# MainPSU.net
KiCad netlist of a schematic drawn in EAGLE
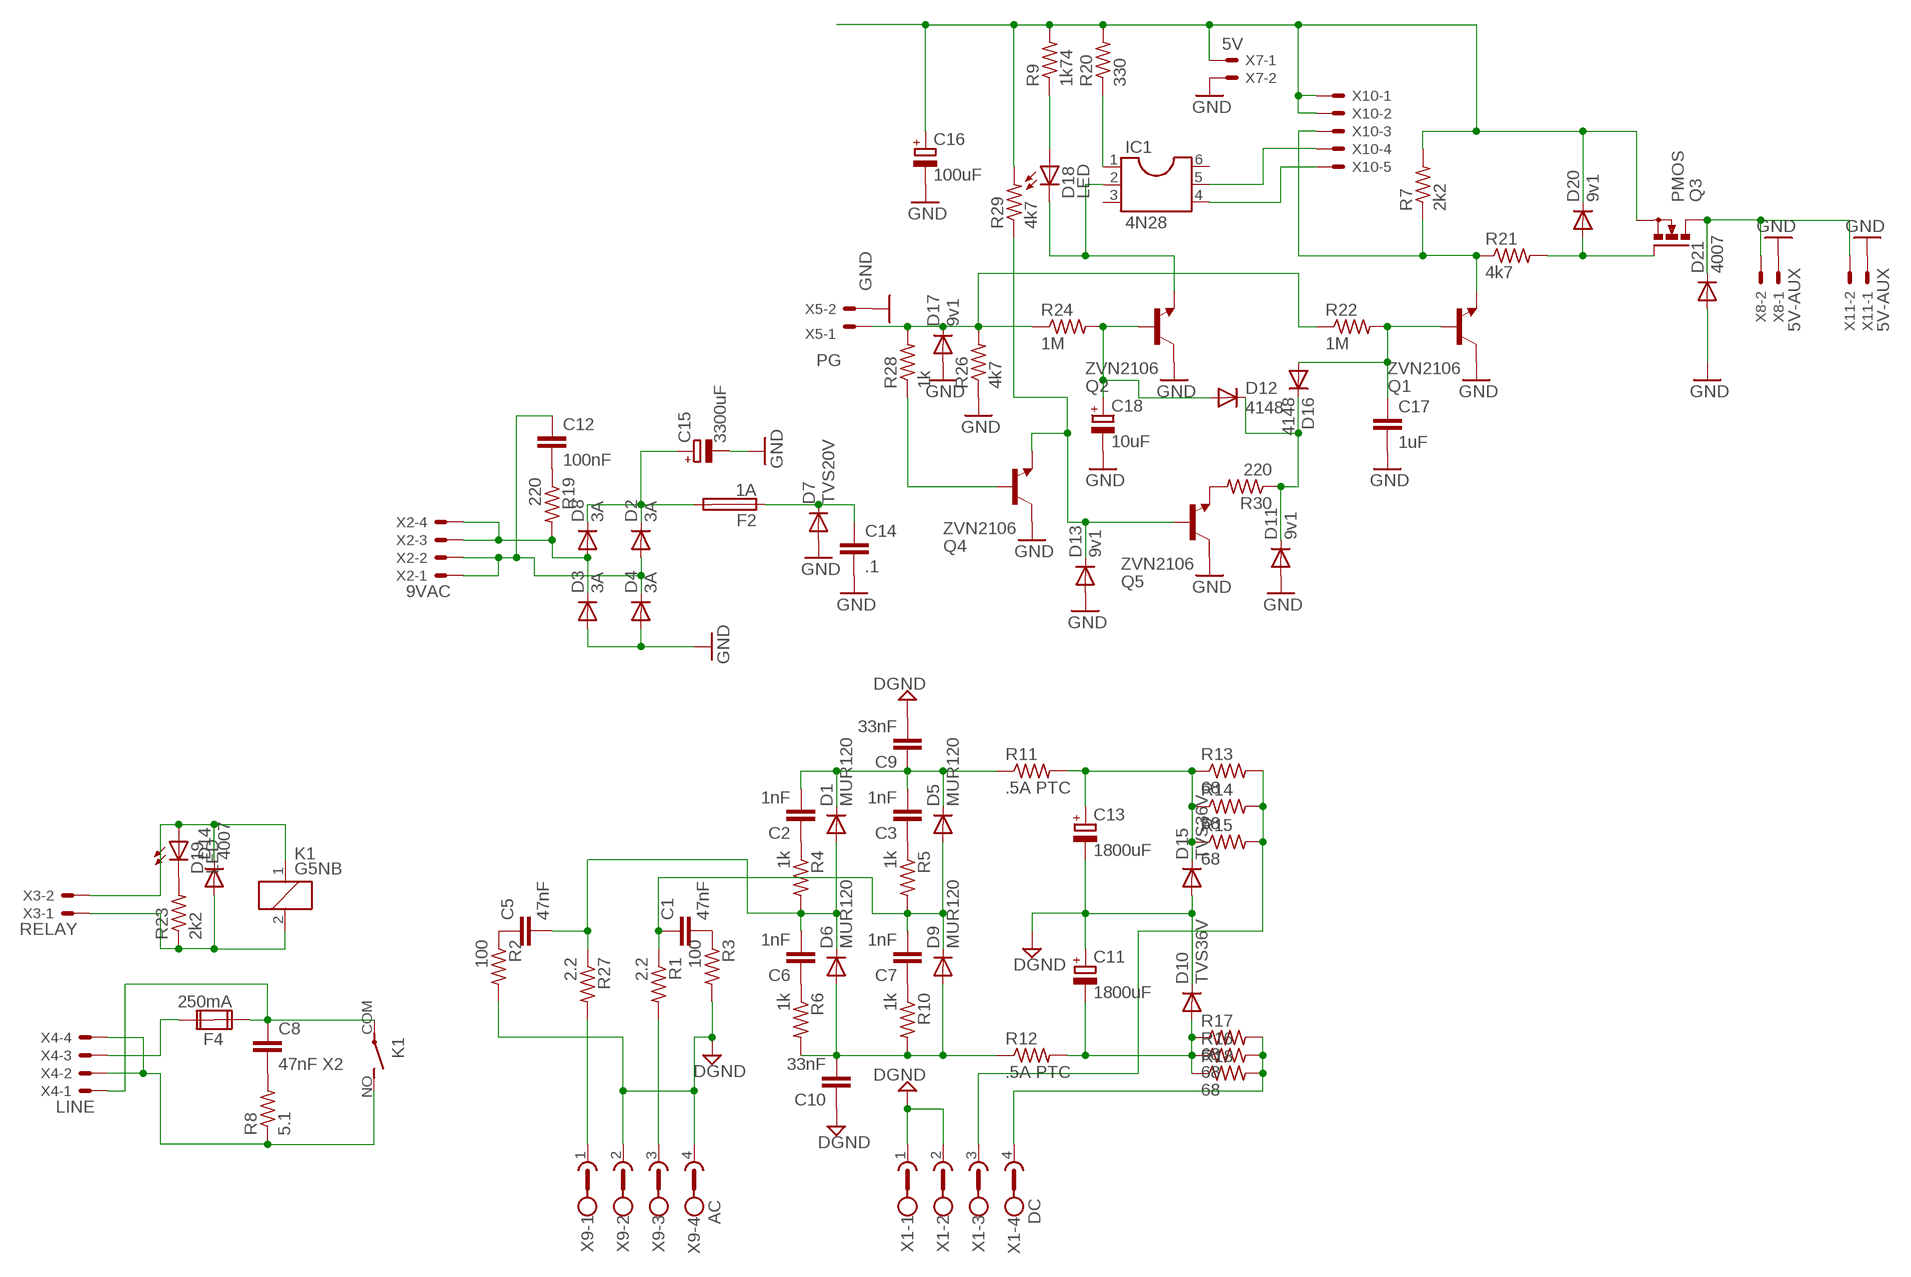
[diagram p0: schematic, sheet 1]

(export (version "E")
  (design (tool "Eeschema 10.0.6"))
  (components
    (comp (ref "C1")
      (value "47nF")
      (footprint "eagle-import:C050-075X075")
      (libsource (lib "eagle-import") (part "C-EU050-075X075"))
    )
    (comp (ref "C2")
      (value "1nF")
      (footprint "eagle-import:C075-042X103")
      (libsource (lib "eagle-import") (part "C-EU075-042X103"))
    )
    (comp (ref "C3")
      (value "1nF")
      (footprint "eagle-import:C075-042X103")
      (libsource (lib "eagle-import") (part "C-EU075-042X103"))
    )
    (comp (ref "C5")
      (value "47nF")
      (footprint "eagle-import:C050-075X075")
      (libsource (lib "eagle-import") (part "C-EU050-075X075"))
    )
    (comp (ref "C6")
      (value "1nF")
      (footprint "eagle-import:C075-042X103")
      (libsource (lib "eagle-import") (part "C-EU075-042X103"))
    )
    (comp (ref "C7")
      (value "1nF")
      (footprint "eagle-import:C075-042X103")
      (libsource (lib "eagle-import") (part "C-EU075-042X103"))
    )
    (comp (ref "C8")
      (value "47nF X2")
      (footprint "eagle-import:C225-062X268")
      (libsource (lib "eagle-import") (part "C-EU225-062X268"))
    )
    (comp (ref "C9")
      (value "33nF")
      (footprint "eagle-import:C050-075X075")
      (libsource (lib "eagle-import") (part "C-EU050-075X075"))
    )
    (comp (ref "C10")
      (value "33nF")
      (footprint "eagle-import:C050-075X075")
      (libsource (lib "eagle-import") (part "C-EU050-075X075"))
    )
    (comp (ref "C11")
      (value "1800uF")
      (footprint "eagle-import:E7,5-16")
      (libsource (lib "eagle-import") (part "CPOL-EUE7.5-16"))
    )
    (comp (ref "C12")
      (value "100nF")
      (footprint "eagle-import:C050-075X075")
      (libsource (lib "eagle-import") (part "C-EU050-075X075"))
    )
    (comp (ref "C13")
      (value "1800uF")
      (footprint "eagle-import:E7,5-16")
      (libsource (lib "eagle-import") (part "CPOL-EUE7.5-16"))
    )
    (comp (ref "C14")
      (value ".1")
      (footprint "eagle-import:C1812")
      (libsource (lib "eagle-import") (part "C-EUC1812"))
    )
    (comp (ref "C15")
      (value "3300uF")
      (footprint "eagle-import:E7,5-16")
      (libsource (lib "eagle-import") (part "CPOL-EUE7.5-16"))
    )
    (comp (ref "C16")
      (value "100uF")
      (footprint "eagle-import:E3,5-10")
      (libsource (lib "eagle-import") (part "CPOL-EUE3.5-10"))
    )
    (comp (ref "C17")
      (value "1uF")
      (footprint "eagle-import:C1812")
      (libsource (lib "eagle-import") (part "C-EUC1812"))
    )
    (comp (ref "C18")
      (value "10uF")
      (footprint "eagle-import:E2,5-6E")
      (libsource (lib "eagle-import") (part "CPOL-EUE2,5-6E"))
    )
    (comp (ref "D1")
      (value "MUR120")
      (footprint "eagle-import:DO41-10")
      (libsource (lib "eagle-import") (part "1N4004"))
    )
    (comp (ref "D2")
      (value "3A")
      (footprint "eagle-import:DO220S")
      (libsource (lib "eagle-import") (part "BYW29"))
    )
    (comp (ref "D3")
      (value "3A")
      (footprint "eagle-import:DO220S")
      (libsource (lib "eagle-import") (part "BYW29"))
    )
    (comp (ref "D4")
      (value "3A")
      (footprint "eagle-import:DO220S")
      (libsource (lib "eagle-import") (part "BYW29"))
    )
    (comp (ref "D5")
      (value "MUR120")
      (footprint "eagle-import:DO41-10")
      (libsource (lib "eagle-import") (part "1N4004"))
    )
    (comp (ref "D6")
      (value "MUR120")
      (footprint "eagle-import:DO41-10")
      (libsource (lib "eagle-import") (part "1N4004"))
    )
    (comp (ref "D7")
      (value "TVS20V")
      (footprint "eagle-import:SOD57-10")
      (libsource (lib "eagle-import") (part "BY448"))
    )
    (comp (ref "D8")
      (value "3A")
      (footprint "eagle-import:DO41-10")
      (libsource (lib "eagle-import") (part "1N4004"))
    )
    (comp (ref "D9")
      (value "MUR120")
      (footprint "eagle-import:DO41-10")
      (libsource (lib "eagle-import") (part "1N4004"))
    )
    (comp (ref "D10")
      (value "TVS36V")
      (footprint "eagle-import:SOD57-10")
      (libsource (lib "eagle-import") (part "BY448"))
    )
    (comp (ref "D11")
      (value "9v1")
      (footprint "eagle-import:DO35-7")
      (libsource (lib "eagle-import") (part "1N4148DO35-7"))
    )
    (comp (ref "D12")
      (value "4148")
      (footprint "eagle-import:DO35-7")
      (libsource (lib "eagle-import") (part "1N4148DO35-7"))
    )
    (comp (ref "D13")
      (value "9v1")
      (footprint "eagle-import:DO35-7")
      (libsource (lib "eagle-import") (part "1N4148DO35-7"))
    )
    (comp (ref "D14")
      (value "4007")
      (footprint "eagle-import:DO35-10")
      (libsource (lib "eagle-import") (part "1N4148DO35-10"))
    )
    (comp (ref "D15")
      (value "TVS36V")
      (footprint "eagle-import:SOD57-10")
      (libsource (lib "eagle-import") (part "BY448"))
    )
    (comp (ref "D16")
      (value "4148")
      (footprint "eagle-import:DO35-7")
      (libsource (lib "eagle-import") (part "1N4148DO35-7"))
    )
    (comp (ref "D17")
      (value "9v1")
      (footprint "eagle-import:DO35-7")
      (libsource (lib "eagle-import") (part "1N4148DO35-7"))
    )
    (comp (ref "D18")
      (value "LED")
      (footprint "eagle-import:SFH482")
      (libsource (lib "eagle-import") (part "SFH482"))
    )
    (comp (ref "D19")
      (value "LED")
      (footprint "eagle-import:SFH482")
      (libsource (lib "eagle-import") (part "SFH482"))
    )
    (comp (ref "D20")
      (value "9v1")
      (footprint "eagle-import:DO35-10")
      (libsource (lib "eagle-import") (part "1N4148DO35-10"))
    )
    (comp (ref "D21")
      (value "4007")
      (footprint "eagle-import:DO41-10")
      (libsource (lib "eagle-import") (part "1N4004"))
    )
    (comp (ref "F2")
      (value "1A")
      (footprint "eagle-import:19560")
      (fields (field (name "MPN") "56000001009"))
      (libsource (lib "eagle-import") (part "19560"))
    )
    (comp (ref "F4")
      (value "250mA")
      (footprint "eagle-import:FUSE1")
      (libsource (lib "eagle-import") (part "FUSE2P"))
    )
    (comp (ref "IC1")
      (value "4N28")
      (footprint "eagle-import:DIL06")
      (libsource (lib "eagle-import") (part "DIL6"))
    )
    (comp (ref "K1")
      (value "G5NB")
      (footprint "eagle-import:LD")
      (libsource (lib "eagle-import") (part "LD?14H"))
    )
    (comp (ref "Q1")
      (value "ZVN2106")
      (footprint "eagle-import:TO92-EBC")
      (libsource (lib "eagle-import") (part "BC550B"))
    )
    (comp (ref "Q2")
      (value "ZVN2106")
      (footprint "eagle-import:TO92-EBC")
      (libsource (lib "eagle-import") (part "BC550B"))
    )
    (comp (ref "Q3")
      (value "PMOS")
      (footprint "eagle-import:TO220BV")
      (libsource (lib "eagle-import") (part "BUZ11BV"))
    )
    (comp (ref "Q4")
      (value "ZVN2106")
      (footprint "eagle-import:TO92-EBC")
      (libsource (lib "eagle-import") (part "BC550B"))
    )
    (comp (ref "Q5")
      (value "ZVN2106")
      (footprint "eagle-import:TO92-EBC")
      (libsource (lib "eagle-import") (part "BC550B"))
    )
    (comp (ref "R1")
      (value "2.2")
      (footprint "eagle-import:0617V")
      (libsource (lib "eagle-import") (part "R-US_0617/5V"))
    )
    (comp (ref "R2")
      (value "100")
      (footprint "eagle-import:0309_12")
      (libsource (lib "eagle-import") (part "R-US_0309/12"))
    )
    (comp (ref "R3")
      (value "100")
      (footprint "eagle-import:0207_5V")
      (libsource (lib "eagle-import") (part "R-US_0207/5V"))
    )
    (comp (ref "R4")
      (value "1k")
      (footprint "eagle-import:0207_7")
      (libsource (lib "eagle-import") (part "R-US_0207/7"))
    )
    (comp (ref "R5")
      (value "1k")
      (footprint "eagle-import:0207_7")
      (libsource (lib "eagle-import") (part "R-US_0207/7"))
    )
    (comp (ref "R6")
      (value "1k")
      (footprint "eagle-import:0309_10")
      (libsource (lib "eagle-import") (part "R-US_0309/10"))
    )
    (comp (ref "R7")
      (value "2k2")
      (footprint "eagle-import:0309_10")
      (libsource (lib "eagle-import") (part "R-US_0309/10"))
    )
    (comp (ref "R8")
      (value "5.1")
      (footprint "eagle-import:0309_10")
      (libsource (lib "eagle-import") (part "R-US_0309/10"))
    )
    (comp (ref "R9")
      (value "1k74")
      (footprint "eagle-import:0309_10")
      (libsource (lib "eagle-import") (part "R-US_0309/10"))
    )
    (comp (ref "R10")
      (value "1k")
      (footprint "eagle-import:0207_7")
      (libsource (lib "eagle-import") (part "R-US_0207/7"))
    )
    (comp (ref "R11")
      (value ".5A PTC")
      (footprint "eagle-import:0207_7")
      (libsource (lib "eagle-import") (part "R-US_0207/7"))
    )
    (comp (ref "R12")
      (value ".5A PTC")
      (footprint "eagle-import:0207_7")
      (libsource (lib "eagle-import") (part "R-US_0207/7"))
    )
    (comp (ref "R13")
      (value "68")
      (footprint "eagle-import:0411_15")
      (libsource (lib "eagle-import") (part "R-US_0411/15"))
    )
    (comp (ref "R14")
      (value "68")
      (footprint "eagle-import:0411_15")
      (libsource (lib "eagle-import") (part "R-US_0411/15"))
    )
    (comp (ref "R15")
      (value "68")
      (footprint "eagle-import:0411_15")
      (libsource (lib "eagle-import") (part "R-US_0411/15"))
    )
    (comp (ref "R16")
      (value "68")
      (footprint "eagle-import:0411_15")
      (libsource (lib "eagle-import") (part "R-US_0411/15"))
    )
    (comp (ref "R17")
      (value "68")
      (footprint "eagle-import:0411_15")
      (libsource (lib "eagle-import") (part "R-US_0411/15"))
    )
    (comp (ref "R18")
      (value "68")
      (footprint "eagle-import:0411_15")
      (libsource (lib "eagle-import") (part "R-US_0411/15"))
    )
    (comp (ref "R19")
      (value "220")
      (footprint "eagle-import:0207_15")
      (libsource (lib "eagle-import") (part "R-US_0207/15"))
    )
    (comp (ref "R20")
      (value "330")
      (footprint "eagle-import:0309_10")
      (libsource (lib "eagle-import") (part "R-US_0309/10"))
    )
    (comp (ref "R21")
      (value "4k7")
      (footprint "eagle-import:0309_10")
      (libsource (lib "eagle-import") (part "R-US_0309/10"))
    )
    (comp (ref "R22")
      (value "1M")
      (footprint "eagle-import:0309_10")
      (libsource (lib "eagle-import") (part "R-US_0309/10"))
    )
    (comp (ref "R23")
      (value "2k2")
      (footprint "eagle-import:0309_10")
      (libsource (lib "eagle-import") (part "R-US_0309/10"))
    )
    (comp (ref "R24")
      (value "1M")
      (footprint "eagle-import:0309_10")
      (libsource (lib "eagle-import") (part "R-US_0309/10"))
    )
    (comp (ref "R26")
      (value "4k7")
      (footprint "eagle-import:0309_10")
      (libsource (lib "eagle-import") (part "R-US_0309/10"))
    )
    (comp (ref "R27")
      (value "2.2")
      (footprint "eagle-import:0617V")
      (libsource (lib "eagle-import") (part "R-US_0617/5V"))
    )
    (comp (ref "R28")
      (value "1k")
      (footprint "eagle-import:0309_10")
      (libsource (lib "eagle-import") (part "R-US_0309/10"))
    )
    (comp (ref "R29")
      (value "4k7")
      (footprint "eagle-import:0309_10")
      (libsource (lib "eagle-import") (part "R-US_0309/10"))
    )
    (comp (ref "R30")
      (value "220")
      (footprint "eagle-import:0309_10")
      (libsource (lib "eagle-import") (part "R-US_0309/10"))
    )
    (comp (ref "X1")
      (value "DC")
      (footprint "eagle-import:GMSTBA4")
      (fields (field (name "MF") "FARNELL") (field (name "MPN") "1757268"))
      (libsource (lib "eagle-import") (part "GMSTBA4"))
    )
    (comp (ref "X2")
      (value "9VAC")
      (footprint "eagle-import:5566-4")
      (libsource (lib "eagle-import") (part "5566-4"))
    )
    (comp (ref "X3")
      (value "RELAY")
      (footprint "eagle-import:22-23-2021")
      (fields (field (name "MF") "MOLEX") (field (name "MPN") "22-23-2021"))
      (libsource (lib "eagle-import") (part "22-23-2021"))
    )
    (comp (ref "X4")
      (value "LINE")
      (footprint "eagle-import:5566-4")
      (libsource (lib "eagle-import") (part "5566-4"))
    )
    (comp (ref "X5")
      (value "PG")
      (footprint "eagle-import:22-23-2021")
      (fields (field (name "MF") "MOLEX") (field (name "MPN") "22-23-2021"))
      (libsource (lib "eagle-import") (part "22-23-2021"))
    )
    (comp (ref "X7")
      (value "5V")
      (footprint "eagle-import:22-23-2021")
      (fields (field (name "MF") "MOLEX") (field (name "MPN") "22-23-2021"))
      (libsource (lib "eagle-import") (part "22-23-2021"))
    )
    (comp (ref "X8")
      (value "5V-AUX")
      (footprint "eagle-import:22-23-2021")
      (fields (field (name "MF") "MOLEX") (field (name "MPN") "22-23-2021"))
      (libsource (lib "eagle-import") (part "22-23-2021"))
    )
    (comp (ref "X9")
      (value "AC")
      (footprint "eagle-import:GMSTBA4")
      (fields (field (name "MF") "FARNELL") (field (name "MPN") "1757268"))
      (libsource (lib "eagle-import") (part "GMSTBA4"))
    )
    (comp (ref "X10")
      (value "22-23-2051")
      (footprint "eagle-import:22-23-2051")
      (fields (field (name "MF") "MOLEX"))
      (libsource (lib "eagle-import") (part "22-23-2051"))
    )
    (comp (ref "X11")
      (value "5V-AUX")
      (footprint "eagle-import:22-23-2021")
      (fields (field (name "MF") "MOLEX") (field (name "MPN") "22-23-2021"))
      (libsource (lib "eagle-import") (part "22-23-2021"))
    )
  )
  (nets
    (net (code "1") (name "DGND") (class "Default")
      (node (ref "C10") (pin "1") (pinfunction "1_1") (pintype "passive"))
      (node (ref "C11") (pin "+") (pinfunction "+_+") (pintype "passive"))
      (node (ref "C13") (pin "-") (pinfunction "-_-") (pintype "passive"))
      (node (ref "C9") (pin "2") (pinfunction "2_2") (pintype "passive"))
      (node (ref "D10") (pin "C") (pinfunction "C_C") (pintype "passive"))
      (node (ref "D15") (pin "A") (pinfunction "A_A") (pintype "passive"))
      (node (ref "R2") (pin "2") (pinfunction "2_2") (pintype "passive"))
      (node (ref "R3") (pin "2") (pinfunction "2_2") (pintype "passive"))
      (node (ref "X1") (pin "1") (pinfunction "1_1") (pintype "passive"))
      (node (ref "X1") (pin "2") (pinfunction "1_2") (pintype "passive"))
      (node (ref "X9") (pin "2") (pinfunction "1_2") (pintype "passive"))
      (node (ref "X9") (pin "4") (pinfunction "1_4") (pintype "passive"))
    )
    (net (code "2") (name "GND") (class "Default")
      (node (ref "C14") (pin "2") (pinfunction "2_2") (pintype "passive"))
      (node (ref "C15") (pin "-") (pinfunction "-_-") (pintype "passive"))
      (node (ref "C16") (pin "-") (pinfunction "-_-") (pintype "passive"))
      (node (ref "C17") (pin "2") (pinfunction "2_2") (pintype "passive"))
      (node (ref "C18") (pin "-") (pinfunction "-_-") (pintype "passive"))
      (node (ref "D11") (pin "A") (pinfunction "A_A") (pintype "passive"))
      (node (ref "D13") (pin "A") (pinfunction "A_A") (pintype "passive"))
      (node (ref "D17") (pin "A") (pinfunction "A_A") (pintype "passive"))
      (node (ref "D21") (pin "A") (pinfunction "A_A") (pintype "passive"))
      (node (ref "D3") (pin "A") (pinfunction "A_A") (pintype "passive"))
      (node (ref "D4") (pin "A") (pinfunction "A_A") (pintype "passive"))
      (node (ref "D7") (pin "A") (pinfunction "A_A") (pintype "passive"))
      (node (ref "Q1") (pin "C") (pinfunction "C_C") (pintype "passive"))
      (node (ref "Q2") (pin "C") (pinfunction "C_C") (pintype "passive"))
      (node (ref "Q4") (pin "C") (pinfunction "C_C") (pintype "passive"))
      (node (ref "Q5") (pin "C") (pinfunction "C_C") (pintype "passive"))
      (node (ref "R26") (pin "1") (pinfunction "1_1") (pintype "passive"))
      (node (ref "X11") (pin "1") (pinfunction "S_1") (pintype "passive"))
      (node (ref "X5") (pin "2") (pinfunction "S_2") (pintype "passive"))
      (node (ref "X7") (pin "2") (pinfunction "S_2") (pintype "passive"))
      (node (ref "X8") (pin "1") (pinfunction "S_1") (pintype "passive"))
    )
    (net (code "3") (name "Net-(C1-Pad1)") (class "Default")
      (node (ref "C1") (pin "1") (pinfunction "1_1") (pintype "passive"))
      (node (ref "C7") (pin "2") (pinfunction "2_2") (pintype "passive"))
      (node (ref "D5") (pin "A") (pinfunction "A_A") (pintype "passive"))
      (node (ref "D9") (pin "C") (pinfunction "C_C") (pintype "passive"))
      (node (ref "R1") (pin "1") (pinfunction "1_1") (pintype "passive"))
      (node (ref "R5") (pin "2") (pinfunction "2_2") (pintype "passive"))
    )
    (net (code "4") (name "Net-(C1-Pad2)") (class "Default")
      (node (ref "C1") (pin "2") (pinfunction "2_2") (pintype "passive"))
      (node (ref "R3") (pin "1") (pinfunction "1_1") (pintype "passive"))
    )
    (net (code "5") (name "Net-(C2-Pad1)") (class "Default")
      (node (ref "C2") (pin "1") (pinfunction "1_1") (pintype "passive"))
      (node (ref "R4") (pin "1") (pinfunction "1_1") (pintype "passive"))
    )
    (net (code "6") (name "Net-(C2-Pad2)") (class "Default")
      (node (ref "C2") (pin "2") (pinfunction "2_2") (pintype "passive"))
      (node (ref "C3") (pin "2") (pinfunction "2_2") (pintype "passive"))
      (node (ref "C9") (pin "1") (pinfunction "1_1") (pintype "passive"))
      (node (ref "D1") (pin "C") (pinfunction "C_C") (pintype "passive"))
      (node (ref "D5") (pin "C") (pinfunction "C_C") (pintype "passive"))
      (node (ref "R11") (pin "1") (pinfunction "1_1") (pintype "passive"))
    )
    (net (code "7") (name "Net-(C3-Pad1)") (class "Default")
      (node (ref "C3") (pin "1") (pinfunction "1_1") (pintype "passive"))
      (node (ref "R5") (pin "1") (pinfunction "1_1") (pintype "passive"))
    )
    (net (code "8") (name "Net-(C5-Pad1)") (class "Default")
      (node (ref "C5") (pin "1") (pinfunction "1_1") (pintype "passive"))
      (node (ref "R2") (pin "1") (pinfunction "1_1") (pintype "passive"))
    )
    (net (code "9") (name "Net-(C5-Pad2)") (class "Default")
      (node (ref "C5") (pin "2") (pinfunction "2_2") (pintype "passive"))
      (node (ref "C6") (pin "2") (pinfunction "2_2") (pintype "passive"))
      (node (ref "D1") (pin "A") (pinfunction "A_A") (pintype "passive"))
      (node (ref "D6") (pin "C") (pinfunction "C_C") (pintype "passive"))
      (node (ref "R27") (pin "1") (pinfunction "1_1") (pintype "passive"))
      (node (ref "R4") (pin "2") (pinfunction "2_2") (pintype "passive"))
    )
    (net (code "10") (name "Net-(C6-Pad1)") (class "Default")
      (node (ref "C6") (pin "1") (pinfunction "1_1") (pintype "passive"))
      (node (ref "R6") (pin "1") (pinfunction "1_1") (pintype "passive"))
    )
    (net (code "11") (name "Net-(C7-Pad1)") (class "Default")
      (node (ref "C7") (pin "1") (pinfunction "1_1") (pintype "passive"))
      (node (ref "R10") (pin "1") (pinfunction "1_1") (pintype "passive"))
    )
    (net (code "12") (name "Net-(C8-Pad2)") (class "Default")
      (node (ref "C8") (pin "2") (pinfunction "2_2") (pintype "passive"))
      (node (ref "R8") (pin "2") (pinfunction "2_2") (pintype "passive"))
    )
    (net (code "13") (name "Net-(C10-Pad2)") (class "Default")
      (node (ref "C10") (pin "2") (pinfunction "2_2") (pintype "passive"))
      (node (ref "D6") (pin "A") (pinfunction "A_A") (pintype "passive"))
      (node (ref "D9") (pin "A") (pinfunction "A_A") (pintype "passive"))
      (node (ref "R10") (pin "2") (pinfunction "2_2") (pintype "passive"))
      (node (ref "R12") (pin "1") (pinfunction "1_1") (pintype "passive"))
      (node (ref "R6") (pin "2") (pinfunction "2_2") (pintype "passive"))
    )
    (net (code "14") (name "Net-(C11-Pad-)") (class "Default")
      (node (ref "C11") (pin "-") (pinfunction "-_-") (pintype "passive"))
      (node (ref "D10") (pin "A") (pinfunction "A_A") (pintype "passive"))
      (node (ref "R12") (pin "2") (pinfunction "2_2") (pintype "passive"))
      (node (ref "R16") (pin "1") (pinfunction "1_1") (pintype "passive"))
      (node (ref "R17") (pin "1") (pinfunction "1_1") (pintype "passive"))
      (node (ref "R18") (pin "1") (pinfunction "1_1") (pintype "passive"))
    )
    (net (code "15") (name "Net-(C12-Pad2)") (class "Default")
      (node (ref "C12") (pin "2") (pinfunction "2_2") (pintype "passive"))
      (node (ref "R19") (pin "1") (pinfunction "1_1") (pintype "passive"))
    )
    (net (code "16") (name "Net-(C13-Pad+)") (class "Default")
      (node (ref "C13") (pin "+") (pinfunction "+_+") (pintype "passive"))
      (node (ref "D15") (pin "C") (pinfunction "C_C") (pintype "passive"))
      (node (ref "R11") (pin "2") (pinfunction "2_2") (pintype "passive"))
      (node (ref "R13") (pin "1") (pinfunction "1_1") (pintype "passive"))
      (node (ref "R14") (pin "1") (pinfunction "1_1") (pintype "passive"))
      (node (ref "R15") (pin "1") (pinfunction "1_1") (pintype "passive"))
    )
    (net (code "17") (name "Net-(C14-Pad1)") (class "Default")
      (node (ref "C14") (pin "1") (pinfunction "1_1") (pintype "passive"))
      (node (ref "D7") (pin "C") (pinfunction "C_C") (pintype "passive"))
      (node (ref "F2") (pin "1") (pinfunction "1_1") (pintype "passive"))
    )
    (net (code "18") (name "Net-(C15-Pad+)") (class "Default")
      (node (ref "C15") (pin "+") (pinfunction "+_+") (pintype "passive"))
      (node (ref "D2") (pin "C") (pinfunction "C_C") (pintype "passive"))
      (node (ref "D8") (pin "C") (pinfunction "C_C") (pintype "passive"))
      (node (ref "F2") (pin "2") (pinfunction "2_2") (pintype "passive"))
    )
    (net (code "19") (name "Net-(C17-Pad1)") (class "Default")
      (node (ref "C17") (pin "1") (pinfunction "1_1") (pintype "passive"))
      (node (ref "D16") (pin "A") (pinfunction "A_A") (pintype "passive"))
      (node (ref "Q1") (pin "B") (pinfunction "B_B") (pintype "passive"))
      (node (ref "R22") (pin "2") (pinfunction "2_2") (pintype "passive"))
    )
    (net (code "20") (name "Net-(C18-Pad+)") (class "Default")
      (node (ref "C18") (pin "+") (pinfunction "+_+") (pintype "passive"))
      (node (ref "D12") (pin "A") (pinfunction "A_A") (pintype "passive"))
      (node (ref "Q2") (pin "B") (pinfunction "B_B") (pintype "passive"))
      (node (ref "R24") (pin "2") (pinfunction "2_2") (pintype "passive"))
    )
    (net (code "21") (name "Net-(D11-PadC)") (class "Default")
      (node (ref "D11") (pin "C") (pinfunction "C_C") (pintype "passive"))
      (node (ref "D12") (pin "C") (pinfunction "C_C") (pintype "passive"))
      (node (ref "D16") (pin "C") (pinfunction "C_C") (pintype "passive"))
      (node (ref "R30") (pin "1") (pinfunction "1_1") (pintype "passive"))
    )
    (net (code "22") (name "Net-(D13-PadC)") (class "Default")
      (node (ref "D13") (pin "C") (pinfunction "C_C") (pintype "passive"))
      (node (ref "Q4") (pin "E") (pinfunction "E_E") (pintype "passive"))
      (node (ref "Q5") (pin "B") (pinfunction "B_B") (pintype "passive"))
      (node (ref "R29") (pin "1") (pinfunction "1_1") (pintype "passive"))
    )
    (net (code "23") (name "Net-(D18-C)") (class "Default")
      (node (ref "D18") (pin "K") (pinfunction "C_K") (pintype "passive"))
      (node (ref "IC1") (pin "2") (pinfunction "2_2") (pintype "passive"))
      (node (ref "Q2") (pin "E") (pinfunction "E_E") (pintype "passive"))
    )
    (net (code "24") (name "Net-(D18-PadA)") (class "Default")
      (node (ref "D18") (pin "A") (pinfunction "A_A") (pintype "passive"))
      (node (ref "R9") (pin "1") (pinfunction "1_1") (pintype "passive"))
    )
    (net (code "25") (name "Net-(D19-C)") (class "Default")
      (node (ref "D19") (pin "K") (pinfunction "C_K") (pintype "passive"))
      (node (ref "R23") (pin "2") (pinfunction "2_2") (pintype "passive"))
    )
    (net (code "26") (name "Net-(D20-PadA)") (class "Default")
      (node (ref "D20") (pin "A") (pinfunction "A_A") (pintype "passive"))
      (node (ref "Q3") (pin "G") (pinfunction "G_G") (pintype "passive"))
      (node (ref "R21") (pin "2") (pinfunction "2_2") (pintype "passive"))
    )
    (net (code "27") (name "Net-(IC1-Pad1)") (class "Default")
      (node (ref "IC1") (pin "1") (pinfunction "1_1") (pintype "passive"))
      (node (ref "R20") (pin "1") (pinfunction "1_1") (pintype "passive"))
    )
    (net (code "28") (name "Net-(K1B-P)") (class "Default")
      (node (ref "C8") (pin "1") (pinfunction "1_1") (pintype "passive"))
      (node (ref "F4") (pin "1A") (pinfunction "1A_1A") (pintype "passive"))
      (node (ref "K1") (pin "COM") (pinfunction "P_COM") (pintype "passive"))
      (node (ref "X4") (pin "1") (pinfunction "S_1") (pintype "passive"))
    )
    (net (code "29") (name "Net-(K1B-S)") (class "Default")
      (node (ref "K1") (pin "NO") (pinfunction "S_NO") (pintype "passive"))
      (node (ref "R8") (pin "1") (pinfunction "1_1") (pintype "passive"))
      (node (ref "X4") (pin "2") (pinfunction "S_2") (pintype "passive"))
      (node (ref "X4") (pin "4") (pinfunction "S_4") (pintype "passive"))
    )
    (net (code "30") (name "Net-(Q4-PadB)") (class "Default")
      (node (ref "Q4") (pin "B") (pinfunction "B_B") (pintype "passive"))
      (node (ref "R28") (pin "1") (pinfunction "1_1") (pintype "passive"))
    )
    (net (code "31") (name "Net-(Q5-PadE)") (class "Default")
      (node (ref "Q5") (pin "E") (pinfunction "E_E") (pintype "passive"))
      (node (ref "R30") (pin "2") (pinfunction "2_2") (pintype "passive"))
    )
    (net (code "32") (name "Net-(R27-Pad2)") (class "Default")
      (node (ref "R27") (pin "2") (pinfunction "2_2") (pintype "passive"))
      (node (ref "X9") (pin "1") (pinfunction "1_1") (pintype "passive"))
    )
    (net (code "33") (name "Net-(X1C-1)") (class "Default")
      (node (ref "R13") (pin "2") (pinfunction "2_2") (pintype "passive"))
      (node (ref "R14") (pin "2") (pinfunction "2_2") (pintype "passive"))
      (node (ref "R15") (pin "2") (pinfunction "2_2") (pintype "passive"))
      (node (ref "X1") (pin "3") (pinfunction "1_3") (pintype "passive"))
    )
    (net (code "34") (name "Net-(X1D-1)") (class "Default")
      (node (ref "R16") (pin "2") (pinfunction "2_2") (pintype "passive"))
      (node (ref "R17") (pin "2") (pinfunction "2_2") (pintype "passive"))
      (node (ref "R18") (pin "2") (pinfunction "2_2") (pintype "passive"))
      (node (ref "X1") (pin "4") (pinfunction "1_4") (pintype "passive"))
    )
    (net (code "35") (name "Net-(X2A-S)") (class "Default")
      (node (ref "C12") (pin "1") (pinfunction "1_1") (pintype "passive"))
      (node (ref "D2") (pin "A") (pinfunction "A_A") (pintype "passive"))
      (node (ref "D4") (pin "C") (pinfunction "C_C") (pintype "passive"))
      (node (ref "X2") (pin "1") (pinfunction "S_1") (pintype "passive"))
      (node (ref "X2") (pin "2") (pinfunction "S_2") (pintype "passive"))
    )
    (net (code "36") (name "Net-(X2C-S)") (class "Default")
      (node (ref "D3") (pin "C") (pinfunction "C_C") (pintype "passive"))
      (node (ref "D8") (pin "A") (pinfunction "A_A") (pintype "passive"))
      (node (ref "R19") (pin "2") (pinfunction "2_2") (pintype "passive"))
      (node (ref "X2") (pin "3") (pinfunction "S_3") (pintype "passive"))
      (node (ref "X2") (pin "4") (pinfunction "S_4") (pintype "passive"))
    )
    (net (code "37") (name "Net-(X3A-S)") (class "Default")
      (node (ref "D14") (pin "A") (pinfunction "A_A") (pintype "passive"))
      (node (ref "K1") (pin "2") (pinfunction "2_2") (pintype "passive"))
      (node (ref "R23") (pin "1") (pinfunction "1_1") (pintype "passive"))
      (node (ref "X3") (pin "1") (pinfunction "S_1") (pintype "passive"))
    )
    (net (code "38") (name "Net-(X3B-S)") (class "Default")
      (node (ref "D14") (pin "C") (pinfunction "C_C") (pintype "passive"))
      (node (ref "D19") (pin "A") (pinfunction "A_A") (pintype "passive"))
      (node (ref "K1") (pin "1") (pinfunction "1_1") (pintype "passive"))
      (node (ref "X3") (pin "2") (pinfunction "S_2") (pintype "passive"))
    )
    (net (code "39") (name "Net-(X4C-S)") (class "Default")
      (node (ref "F4") (pin "2A") (pinfunction "2A_2A") (pintype "passive"))
      (node (ref "X4") (pin "3") (pinfunction "S_3") (pintype "passive"))
    )
    (net (code "40") (name "Net-(X5A-S)") (class "Default")
      (node (ref "D17") (pin "C") (pinfunction "C_C") (pintype "passive"))
      (node (ref "R22") (pin "1") (pinfunction "1_1") (pintype "passive"))
      (node (ref "R24") (pin "1") (pinfunction "1_1") (pintype "passive"))
      (node (ref "R26") (pin "2") (pinfunction "2_2") (pintype "passive"))
      (node (ref "R28") (pin "2") (pinfunction "2_2") (pintype "passive"))
      (node (ref "X5") (pin "1") (pinfunction "S_1") (pintype "passive"))
    )
    (net (code "41") (name "Net-(X9C-1)") (class "Default")
      (node (ref "R1") (pin "2") (pinfunction "2_2") (pintype "passive"))
      (node (ref "X9") (pin "3") (pinfunction "1_3") (pintype "passive"))
    )
    (net (code "42") (name "Net-(X10A-S)") (class "Default")
      (node (ref "C16") (pin "+") (pinfunction "+_+") (pintype "passive"))
      (node (ref "D20") (pin "C") (pinfunction "C_C") (pintype "passive"))
      (node (ref "Q3") (pin "S") (pinfunction "S_S") (pintype "passive"))
      (node (ref "R20") (pin "2") (pinfunction "2_2") (pintype "passive"))
      (node (ref "R29") (pin "2") (pinfunction "2_2") (pintype "passive"))
      (node (ref "R7") (pin "2") (pinfunction "2_2") (pintype "passive"))
      (node (ref "R9") (pin "2") (pinfunction "2_2") (pintype "passive"))
      (node (ref "X10") (pin "1") (pinfunction "S_1") (pintype "passive"))
      (node (ref "X10") (pin "2") (pinfunction "S_2") (pintype "passive"))
      (node (ref "X7") (pin "1") (pinfunction "S_1") (pintype "passive"))
    )
    (net (code "43") (name "Net-(X10C-S)") (class "Default")
      (node (ref "Q1") (pin "E") (pinfunction "E_E") (pintype "passive"))
      (node (ref "R21") (pin "1") (pinfunction "1_1") (pintype "passive"))
      (node (ref "R7") (pin "1") (pinfunction "1_1") (pintype "passive"))
      (node (ref "X10") (pin "3") (pinfunction "S_3") (pintype "passive"))
    )
    (net (code "44") (name "Net-(X10D-S)") (class "Default")
      (node (ref "IC1") (pin "5") (pinfunction "5_5") (pintype "passive"))
      (node (ref "X10") (pin "4") (pinfunction "S_4") (pintype "passive"))
    )
    (net (code "45") (name "Net-(X10E-S)") (class "Default")
      (node (ref "IC1") (pin "4") (pinfunction "4_4") (pintype "passive"))
      (node (ref "X10") (pin "5") (pinfunction "S_5") (pintype "passive"))
    )
    (net (code "46") (name "Net-(X11B-S)") (class "Default")
      (node (ref "D21") (pin "C") (pinfunction "C_C") (pintype "passive"))
      (node (ref "Q3") (pin "D") (pinfunction "D_D") (pintype "passive"))
      (node (ref "X11") (pin "2") (pinfunction "S_2") (pintype "passive"))
      (node (ref "X8") (pin "2") (pinfunction "S_2") (pintype "passive"))
    )
    (net (code "47") (name "unconnected-(F4-Pad1B)") (class "Default")
      (node (ref "F4") (pin "1B") (pinfunction "1B_1B") (pintype "passive"))
    )
    (net (code "48") (name "unconnected-(F4-Pad2B)") (class "Default")
      (node (ref "F4") (pin "2B") (pinfunction "2B_2B") (pintype "passive"))
    )
    (net (code "49") (name "unconnected-(IC1-Pad3)") (class "Default")
      (node (ref "IC1") (pin "3") (pinfunction "3_3") (pintype "passive"))
    )
    (net (code "50") (name "unconnected-(IC1-Pad6)") (class "Default")
      (node (ref "IC1") (pin "6") (pinfunction "6_6") (pintype "passive"))
    )
  )
)
